# TrueTouch.net
KiCad netlist of a schematic drawn in Altium Designer
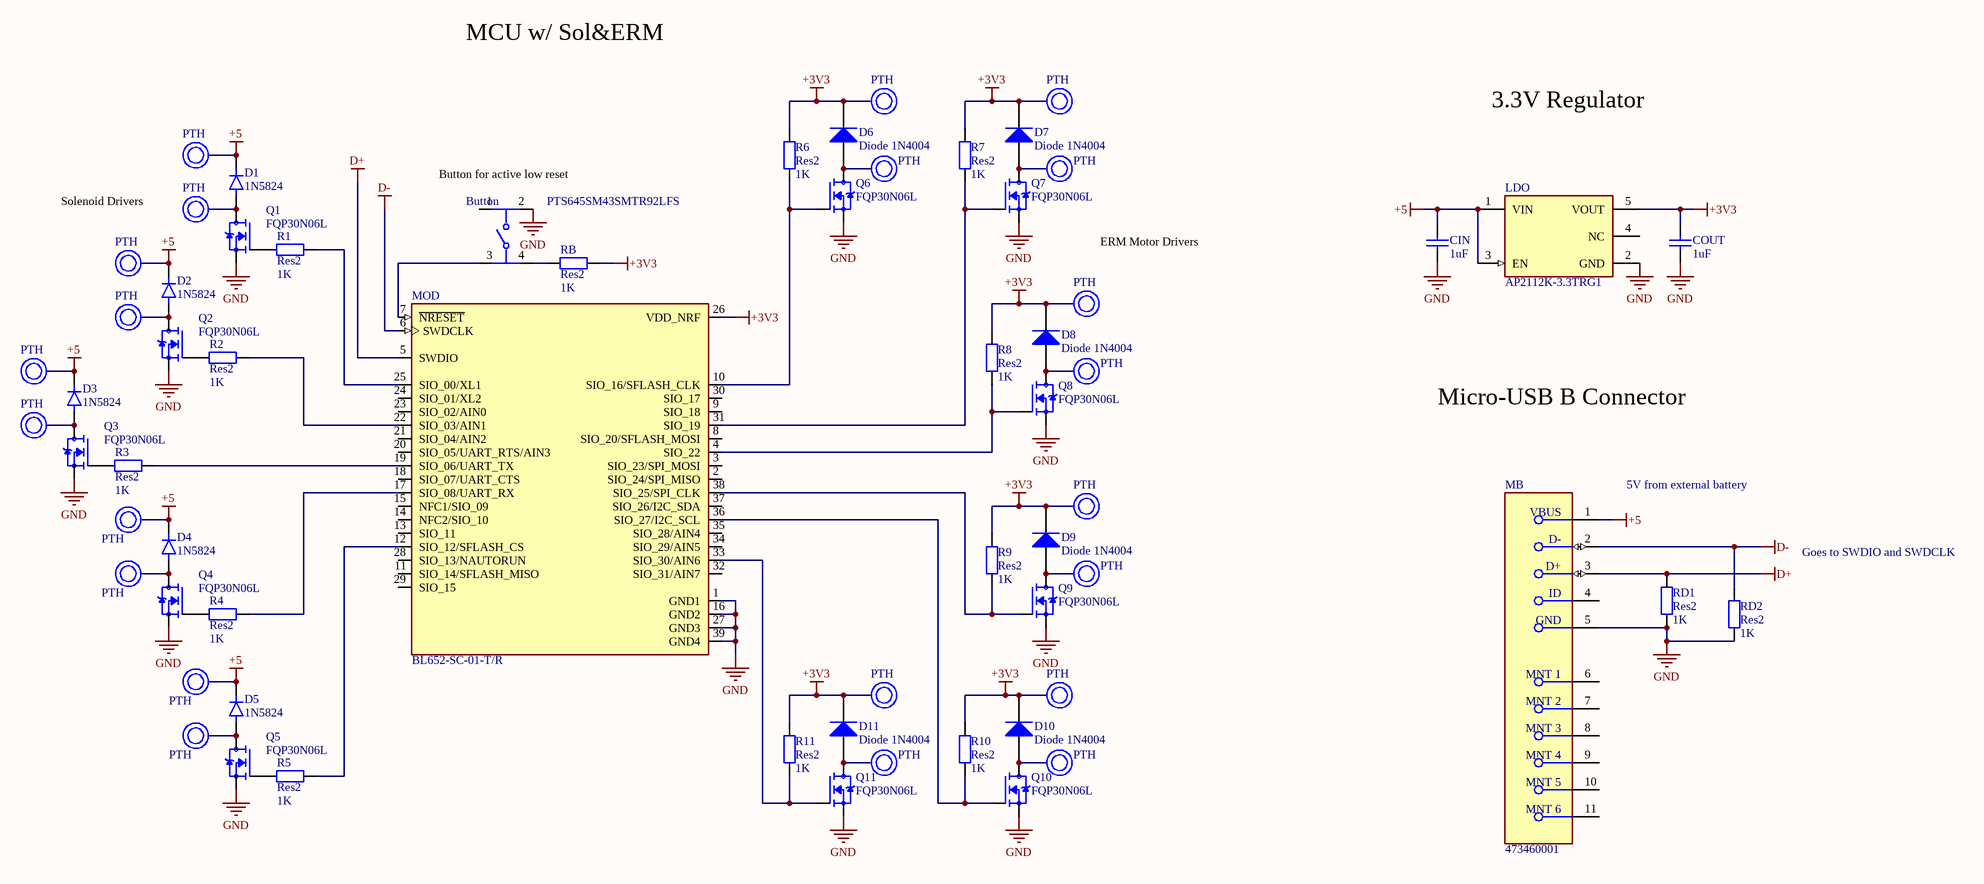
[diagram p0: TrueTouch.SchDoc]

(export (version "E")
  (design (tool "Eeschema 10.0.6"))
  (components
    (comp (ref "Button")
      (value "PTS645SM43SMTR92LFS")
      (footprint "FP-PTS645SM43SMTR92LFS-MFG")
      (description "SWITCH TACTILE SPST-NO 0.05A 12V")
      (libsource (lib "Altium Content Vault") (part "1adf0dd01260c80cf25a44bfd6b99ba"))
    )
    (comp (ref "CIN")
      (value "1uF")
      (footprint "CAPC2013X140X45NL15T25")
      (fields (field (name "PART NUMBER") "GRM21BR71E105KA99L") (field (name "MANUFACTURER") "Murata"))
      (libsource (lib "Altium Content Vault") (part "CAP"))
    )
    (comp (ref "COUT")
      (value "1uF")
      (footprint "CAPC2013X140X45NL15T25")
      (fields (field (name "PART NUMBER") "GRM21BR71E105KA99L") (field (name "MANUFACTURER") "Murata"))
      (libsource (lib "Altium Content Vault") (part "CAP"))
    )
    (comp (ref "D1")
      (value "1N5824")
      (footprint "DIOAD1898W129L762D1143")
      (description "Diode Schottky 30V 5A Through Hole Axial")
      (fields (field (name "MF") "Microsemi Corporation"))
      (libsource (lib "1N5824") (part "1N5824"))
    )
    (comp (ref "D2")
      (value "1N5824")
      (footprint "DIOAD1898W129L762D1143")
      (description "Diode Schottky 30V 5A Through Hole Axial")
      (fields (field (name "MF") "Microsemi Corporation"))
      (libsource (lib "1N5824") (part "1N5824"))
    )
    (comp (ref "D3")
      (value "1N5824")
      (footprint "DIOAD1898W129L762D1143")
      (description "Diode Schottky 30V 5A Through Hole Axial")
      (fields (field (name "MF") "Microsemi Corporation"))
      (libsource (lib "1N5824") (part "1N5824"))
    )
    (comp (ref "D4")
      (value "1N5824")
      (footprint "DIOAD1898W129L762D1143")
      (description "Diode Schottky 30V 5A Through Hole Axial")
      (fields (field (name "MF") "Microsemi Corporation"))
      (libsource (lib "1N5824") (part "1N5824"))
    )
    (comp (ref "D5")
      (value "1N5824")
      (footprint "DIOAD1898W129L762D1143")
      (description "Diode Schottky 30V 5A Through Hole Axial")
      (fields (field (name "MF") "Microsemi Corporation"))
      (libsource (lib "1N5824") (part "1N5824"))
    )
    (comp (ref "D6")
      (value "Diode 1N4004")
      (footprint "DO-41")
      (description "1 Amp General Purpose Rectifier")
      (fields (field (name "PUBLISHER") "Altium Limited"))
      (libsource (lib "Miscellaneous Devices") (part "Diode 1N4004"))
    )
    (comp (ref "D7")
      (value "Diode 1N4004")
      (footprint "DO-41")
      (description "1 Amp General Purpose Rectifier")
      (fields (field (name "PUBLISHER") "Altium Limited"))
      (libsource (lib "Miscellaneous Devices") (part "Diode 1N4004"))
    )
    (comp (ref "D8")
      (value "Diode 1N4004")
      (footprint "DO-41")
      (description "1 Amp General Purpose Rectifier")
      (fields (field (name "PUBLISHER") "Altium Limited"))
      (libsource (lib "Miscellaneous Devices") (part "Diode 1N4004"))
    )
    (comp (ref "D9")
      (value "Diode 1N4004")
      (footprint "DO-41")
      (description "1 Amp General Purpose Rectifier")
      (fields (field (name "PUBLISHER") "Altium Limited"))
      (libsource (lib "Miscellaneous Devices") (part "Diode 1N4004"))
    )
    (comp (ref "D10")
      (value "Diode 1N4004")
      (footprint "DO-41")
      (description "1 Amp General Purpose Rectifier")
      (fields (field (name "PUBLISHER") "Altium Limited"))
      (libsource (lib "Miscellaneous Devices") (part "Diode 1N4004"))
    )
    (comp (ref "D11")
      (value "Diode 1N4004")
      (footprint "DO-41")
      (description "1 Amp General Purpose Rectifier")
      (fields (field (name "PUBLISHER") "Altium Limited"))
      (libsource (lib "Miscellaneous Devices") (part "Diode 1N4004"))
    )
    (comp (ref "LDO")
      (value "AP2112K-3.3TRG1")
      (footprint "FP-SOT25-IPC_A")
      (description "IC REG LINEAR 3.3V 600MA SOT25")
      (libsource (lib "Altium Content Vault") (part "c8ab751aee5229183125ab046a11caa"))
    )
    (comp (ref "MB")
      (value "473460001")
      (footprint "FP-473460001-MFG")
      (description "CONN RCPT USB2.0 MICRO B SMD R/A")
      (fields
        (field (name "OCTOPART") "https://octopart.com/47346-0001-molex-7164928")
        (field (name "MANUFACTURER") "Molex")
      )
      (libsource (lib "Altium Content Vault") (part "53ae1f1d9b557310b43ca686e5bb76a"))
    )
    (comp (ref "MOD")
      (value "BL652-SC-01-T/R")
      (footprint "XCVR_BL652-SC-01-T/R")
      (description "Bluetooth Bluetooth v5.0 Transceiver Module 2.4GHz Antenna Not Included, I-PEX MHF4 Surface Mount")
      (fields (field (name "DIGI-KEY_PART_NUMBER") "BL652-SC-01-CT-ND") (field (name "MF") "Laird -"))
      (libsource (lib "BL652-SC-01-T_R") (part "BL652-SC-01-T/R"))
    )
    (comp (ref "Q1")
      (value "FQP30N06L")
      (footprint "TO220V")
      (description "N-Channel 60V 32A _Tc_ 79W _Tc_ Through Hole TO-220-3")
      (fields (field (name "MF") "ON Semiconductor"))
      (libsource (lib "FQP30N06L") (part "FQP30N06L"))
    )
    (comp (ref "Q2")
      (value "FQP30N06L")
      (footprint "TO220V")
      (description "N-Channel 60V 32A _Tc_ 79W _Tc_ Through Hole TO-220-3")
      (fields (field (name "MF") "ON Semiconductor"))
      (libsource (lib "FQP30N06L") (part "FQP30N06L"))
    )
    (comp (ref "Q3")
      (value "FQP30N06L")
      (footprint "TO220V")
      (description "N-Channel 60V 32A _Tc_ 79W _Tc_ Through Hole TO-220-3")
      (fields (field (name "MF") "ON Semiconductor"))
      (libsource (lib "FQP30N06L") (part "FQP30N06L"))
    )
    (comp (ref "Q4")
      (value "FQP30N06L")
      (footprint "TO220V")
      (description "N-Channel 60V 32A _Tc_ 79W _Tc_ Through Hole TO-220-3")
      (fields (field (name "MF") "ON Semiconductor"))
      (libsource (lib "FQP30N06L") (part "FQP30N06L"))
    )
    (comp (ref "Q5")
      (value "FQP30N06L")
      (footprint "TO220V")
      (description "N-Channel 60V 32A _Tc_ 79W _Tc_ Through Hole TO-220-3")
      (fields (field (name "MF") "ON Semiconductor"))
      (libsource (lib "FQP30N06L") (part "FQP30N06L"))
    )
    (comp (ref "Q6")
      (value "FQP30N06L")
      (footprint "TO220V")
      (description "N-Channel 60V 32A _Tc_ 79W _Tc_ Through Hole TO-220-3")
      (fields (field (name "MF") "ON Semiconductor"))
      (libsource (lib "FQP30N06L") (part "FQP30N06L"))
    )
    (comp (ref "Q7")
      (value "FQP30N06L")
      (footprint "TO220V")
      (description "N-Channel 60V 32A _Tc_ 79W _Tc_ Through Hole TO-220-3")
      (fields (field (name "MF") "ON Semiconductor"))
      (libsource (lib "FQP30N06L") (part "FQP30N06L"))
    )
    (comp (ref "Q8")
      (value "FQP30N06L")
      (footprint "TO220V")
      (description "N-Channel 60V 32A _Tc_ 79W _Tc_ Through Hole TO-220-3")
      (fields (field (name "MF") "ON Semiconductor"))
      (libsource (lib "FQP30N06L") (part "FQP30N06L"))
    )
    (comp (ref "Q9")
      (value "FQP30N06L")
      (footprint "TO220V")
      (description "N-Channel 60V 32A _Tc_ 79W _Tc_ Through Hole TO-220-3")
      (fields (field (name "MF") "ON Semiconductor"))
      (libsource (lib "FQP30N06L") (part "FQP30N06L"))
    )
    (comp (ref "Q10")
      (value "FQP30N06L")
      (footprint "TO220V")
      (description "N-Channel 60V 32A _Tc_ 79W _Tc_ Through Hole TO-220-3")
      (fields (field (name "MF") "ON Semiconductor"))
      (libsource (lib "FQP30N06L") (part "FQP30N06L"))
    )
    (comp (ref "Q11")
      (value "FQP30N06L")
      (footprint "TO220V")
      (description "N-Channel 60V 32A _Tc_ 79W _Tc_ Through Hole TO-220-3")
      (fields (field (name "MF") "ON Semiconductor"))
      (libsource (lib "FQP30N06L") (part "FQP30N06L"))
    )
    (comp (ref "R1")
      (value "Res2")
      (footprint "AXIAL-0.4")
      (description "Resistor")
      (fields (field (name "ALTIUM_VALUE") "1K") (field (name "PUBLISHER") "Altium Limited"))
      (libsource (lib "") (part "Res2_1"))
    )
    (comp (ref "R2")
      (value "Res2")
      (footprint "AXIAL-0.4")
      (description "Resistor")
      (fields (field (name "ALTIUM_VALUE") "1K") (field (name "PUBLISHER") "Altium Limited"))
      (libsource (lib "") (part "Res2_1"))
    )
    (comp (ref "R3")
      (value "Res2")
      (footprint "AXIAL-0.4")
      (description "Resistor")
      (fields (field (name "ALTIUM_VALUE") "1K") (field (name "PUBLISHER") "Altium Limited"))
      (libsource (lib "") (part "Res2_1"))
    )
    (comp (ref "R4")
      (value "Res2")
      (footprint "AXIAL-0.4")
      (description "Resistor")
      (fields (field (name "ALTIUM_VALUE") "1K") (field (name "PUBLISHER") "Altium Limited"))
      (libsource (lib "") (part "Res2_1"))
    )
    (comp (ref "R5")
      (value "Res2")
      (footprint "AXIAL-0.4")
      (description "Resistor")
      (fields (field (name "ALTIUM_VALUE") "1K") (field (name "PUBLISHER") "Altium Limited"))
      (libsource (lib "") (part "Res2_1"))
    )
    (comp (ref "R6")
      (value "Res2")
      (footprint "AXIAL-0.4")
      (description "Resistor")
      (fields (field (name "ALTIUM_VALUE") "1K") (field (name "PUBLISHER") "Altium Limited"))
      (libsource (lib "Miscellaneous Devices") (part "Res2"))
    )
    (comp (ref "R7")
      (value "Res2")
      (footprint "AXIAL-0.4")
      (description "Resistor")
      (fields (field (name "ALTIUM_VALUE") "1K") (field (name "PUBLISHER") "Altium Limited"))
      (libsource (lib "Miscellaneous Devices") (part "Res2"))
    )
    (comp (ref "R8")
      (value "Res2")
      (footprint "AXIAL-0.4")
      (description "Resistor")
      (fields (field (name "ALTIUM_VALUE") "1K") (field (name "PUBLISHER") "Altium Limited"))
      (libsource (lib "Miscellaneous Devices") (part "Res2"))
    )
    (comp (ref "R9")
      (value "Res2")
      (footprint "AXIAL-0.4")
      (description "Resistor")
      (fields (field (name "ALTIUM_VALUE") "1K") (field (name "PUBLISHER") "Altium Limited"))
      (libsource (lib "Miscellaneous Devices") (part "Res2"))
    )
    (comp (ref "R10")
      (value "Res2")
      (footprint "AXIAL-0.4")
      (description "Resistor")
      (fields (field (name "ALTIUM_VALUE") "1K") (field (name "PUBLISHER") "Altium Limited"))
      (libsource (lib "Miscellaneous Devices") (part "Res2"))
    )
    (comp (ref "R11")
      (value "Res2")
      (footprint "AXIAL-0.4")
      (description "Resistor")
      (fields (field (name "ALTIUM_VALUE") "1K") (field (name "PUBLISHER") "Altium Limited"))
      (libsource (lib "Miscellaneous Devices") (part "Res2"))
    )
    (comp (ref "RB")
      (value "Res2")
      (footprint "AXIAL-0.4")
      (description "Resistor")
      (fields (field (name "ALTIUM_VALUE") "1K") (field (name "PUBLISHER") "Altium Limited"))
      (libsource (lib "") (part "Res2_1"))
    )
    (comp (ref "RD1")
      (value "Res2")
      (footprint "AXIAL-0.4")
      (description "Resistor")
      (fields (field (name "ALTIUM_VALUE") "1K") (field (name "PUBLISHER") "Altium Limited"))
      (libsource (lib "Miscellaneous Devices") (part "Res2"))
    )
    (comp (ref "RD2")
      (value "Res2")
      (footprint "AXIAL-0.4")
      (description "Resistor")
      (fields (field (name "ALTIUM_VALUE") "1K") (field (name "PUBLISHER") "Altium Limited"))
      (libsource (lib "Miscellaneous Devices") (part "Res2"))
    )
  )
  (nets
    (net (code "1") (name "+3V3") (class "Default")
      (node (ref "COUT") (pin "2") (pinfunction "2_2") (pintype "passive"))
      (node (ref "D10") (pin "2") (pinfunction "K_2") (pintype "passive"))
      (node (ref "D11") (pin "2") (pinfunction "K_2") (pintype "passive"))
      (node (ref "D6") (pin "2") (pinfunction "K_2") (pintype "passive"))
      (node (ref "D7") (pin "2") (pinfunction "K_2") (pintype "passive"))
      (node (ref "D8") (pin "2") (pinfunction "K_2") (pintype "passive"))
      (node (ref "D9") (pin "2") (pinfunction "K_2") (pintype "passive"))
      (node (ref "LDO") (pin "5") (pinfunction "VOUT_5") (pintype "power_in"))
      (node (ref "MOD") (pin "26") (pinfunction "VDD_NRF_26") (pintype "power_in"))
      (node (ref "R10") (pin "1") (pinfunction "1_1") (pintype "passive"))
      (node (ref "R11") (pin "1") (pinfunction "1_1") (pintype "passive"))
      (node (ref "R6") (pin "1") (pinfunction "1_1") (pintype "passive"))
      (node (ref "R7") (pin "1") (pinfunction "1_1") (pintype "passive"))
      (node (ref "R8") (pin "1") (pinfunction "1_1") (pintype "passive"))
      (node (ref "R9") (pin "1") (pinfunction "1_1") (pintype "passive"))
      (node (ref "RB") (pin "2") (pinfunction "2_2") (pintype "passive"))
    )
    (net (code "2") (name "+5") (class "Default")
      (node (ref "CIN") (pin "2") (pinfunction "2_2") (pintype "passive"))
      (node (ref "D1") (pin "C") (pinfunction "K_C") (pintype "passive"))
      (node (ref "D2") (pin "C") (pinfunction "K_C") (pintype "passive"))
      (node (ref "D3") (pin "C") (pinfunction "K_C") (pintype "passive"))
      (node (ref "D4") (pin "C") (pinfunction "K_C") (pintype "passive"))
      (node (ref "D5") (pin "C") (pinfunction "K_C") (pintype "passive"))
      (node (ref "LDO") (pin "1") (pinfunction "VIN_1") (pintype "power_in"))
      (node (ref "LDO") (pin "3") (pinfunction "EN_3") (pintype "input"))
      (node (ref "MB") (pin "1") (pinfunction "VBUS_1") (pintype "power_in"))
    )
    (net (code "3") (name "D+") (class "Default")
      (node (ref "MB") (pin "3") (pinfunction "D+_3") (pintype "bidirectional"))
      (node (ref "MOD") (pin "5") (pinfunction "SWDIO_5") (pintype "bidirectional"))
      (node (ref "RD1") (pin "1") (pinfunction "1_1") (pintype "passive"))
    )
    (net (code "4") (name "D-") (class "Default")
      (node (ref "MB") (pin "2") (pinfunction "D-_2") (pintype "bidirectional"))
      (node (ref "MOD") (pin "6") (pinfunction "SWDCLK_6") (pintype "input"))
      (node (ref "RD2") (pin "1") (pinfunction "1_1") (pintype "passive"))
    )
    (net (code "5") (name "GND") (class "Default")
      (node (ref "Button") (pin "2") (pinfunction "2_2") (pintype "passive"))
      (node (ref "CIN") (pin "1") (pinfunction "1_1") (pintype "passive"))
      (node (ref "COUT") (pin "1") (pinfunction "1_1") (pintype "passive"))
      (node (ref "LDO") (pin "2") (pinfunction "GND_2") (pintype "power_in"))
      (node (ref "MB") (pin "5") (pinfunction "GND_5") (pintype "power_in"))
      (node (ref "MOD") (pin "1") (pinfunction "GND1_1") (pintype "power_in"))
      (node (ref "MOD") (pin "16") (pinfunction "GND2_16") (pintype "power_in"))
      (node (ref "MOD") (pin "27") (pinfunction "GND3_27") (pintype "power_in"))
      (node (ref "MOD") (pin "39") (pinfunction "GND4_39") (pintype "power_in"))
      (node (ref "Q1") (pin "3") (pinfunction "S_3") (pintype "passive"))
      (node (ref "Q10") (pin "3") (pinfunction "S_3") (pintype "passive"))
      (node (ref "Q11") (pin "3") (pinfunction "S_3") (pintype "passive"))
      (node (ref "Q2") (pin "3") (pinfunction "S_3") (pintype "passive"))
      (node (ref "Q3") (pin "3") (pinfunction "S_3") (pintype "passive"))
      (node (ref "Q4") (pin "3") (pinfunction "S_3") (pintype "passive"))
      (node (ref "Q5") (pin "3") (pinfunction "S_3") (pintype "passive"))
      (node (ref "Q6") (pin "3") (pinfunction "S_3") (pintype "passive"))
      (node (ref "Q7") (pin "3") (pinfunction "S_3") (pintype "passive"))
      (node (ref "Q8") (pin "3") (pinfunction "S_3") (pintype "passive"))
      (node (ref "Q9") (pin "3") (pinfunction "S_3") (pintype "passive"))
      (node (ref "RD1") (pin "2") (pinfunction "2_2") (pintype "passive"))
      (node (ref "RD2") (pin "2") (pinfunction "2_2") (pintype "passive"))
    )
    (net (code "6") (name "Net-(Button-Pad4)") (class "Default")
      (node (ref "Button") (pin "4") (pinfunction "4_4") (pintype "passive"))
      (node (ref "RB") (pin "1") (pinfunction "1_1") (pintype "passive"))
    )
    (net (code "7") (name "Net-(D6-A)") (class "Default")
      (node (ref "D6") (pin "1") (pinfunction "A_1") (pintype "passive"))
      (node (ref "Q6") (pin "2") (pinfunction "D_2") (pintype "passive"))
    )
    (net (code "8") (name "Net-(D7-A)") (class "Default")
      (node (ref "D7") (pin "1") (pinfunction "A_1") (pintype "passive"))
      (node (ref "Q7") (pin "2") (pinfunction "D_2") (pintype "passive"))
    )
    (net (code "9") (name "Net-(D8-A)") (class "Default")
      (node (ref "D8") (pin "1") (pinfunction "A_1") (pintype "passive"))
      (node (ref "Q8") (pin "2") (pinfunction "D_2") (pintype "passive"))
    )
    (net (code "10") (name "Net-(D9-A)") (class "Default")
      (node (ref "D9") (pin "1") (pinfunction "A_1") (pintype "passive"))
      (node (ref "Q9") (pin "2") (pinfunction "D_2") (pintype "passive"))
    )
    (net (code "11") (name "Net-(D10-A)") (class "Default")
      (node (ref "D10") (pin "1") (pinfunction "A_1") (pintype "passive"))
      (node (ref "Q10") (pin "2") (pinfunction "D_2") (pintype "passive"))
    )
    (net (code "12") (name "Net-(D11-A)") (class "Default")
      (node (ref "D11") (pin "1") (pinfunction "A_1") (pintype "passive"))
      (node (ref "Q11") (pin "2") (pinfunction "D_2") (pintype "passive"))
    )
    (net (code "13") (name "Net-(MOD-SIO_00{slash}XL1)") (class "Default")
      (node (ref "MOD") (pin "25") (pinfunction "SIO_00/XL1_25") (pintype "bidirectional"))
      (node (ref "R1") (pin "2") (pinfunction "2_2") (pintype "passive"))
    )
    (net (code "14") (name "Net-(MOD-SIO_03{slash}AIN1)") (class "Default")
      (node (ref "MOD") (pin "22") (pinfunction "SIO_03/AIN1_22") (pintype "bidirectional"))
      (node (ref "R2") (pin "2") (pinfunction "2_2") (pintype "passive"))
    )
    (net (code "15") (name "Net-(MOD-SIO_06{slash}UART_TX)") (class "Default")
      (node (ref "MOD") (pin "19") (pinfunction "SIO_06/UART_TX_19") (pintype "bidirectional"))
      (node (ref "R3") (pin "2") (pinfunction "2_2") (pintype "passive"))
    )
    (net (code "16") (name "Net-(MOD-SIO_08{slash}UART_RX)") (class "Default")
      (node (ref "MOD") (pin "17") (pinfunction "SIO_08/UART_RX_17") (pintype "bidirectional"))
      (node (ref "R4") (pin "2") (pinfunction "2_2") (pintype "passive"))
    )
    (net (code "17") (name "Net-(MOD-SIO_12{slash}SFLASH_CS)") (class "Default")
      (node (ref "MOD") (pin "12") (pinfunction "SIO_12/SFLASH_CS_12") (pintype "bidirectional"))
      (node (ref "R5") (pin "2") (pinfunction "2_2") (pintype "passive"))
    )
    (net (code "18") (name "Net-(MOD-SIO_16{slash}SFLASH_CLK)") (class "Default")
      (node (ref "MOD") (pin "10") (pinfunction "SIO_16/SFLASH_CLK_10") (pintype "bidirectional"))
      (node (ref "Q6") (pin "1") (pinfunction "G_1") (pintype "passive"))
      (node (ref "R6") (pin "2") (pinfunction "2_2") (pintype "passive"))
    )
    (net (code "19") (name "Net-(MOD-SIO_19)") (class "Default")
      (node (ref "MOD") (pin "31") (pinfunction "SIO_19_31") (pintype "bidirectional"))
      (node (ref "Q7") (pin "1") (pinfunction "G_1") (pintype "passive"))
      (node (ref "R7") (pin "2") (pinfunction "2_2") (pintype "passive"))
    )
    (net (code "20") (name "Net-(MOD-SIO_22)") (class "Default")
      (node (ref "MOD") (pin "4") (pinfunction "SIO_22_4") (pintype "bidirectional"))
      (node (ref "Q8") (pin "1") (pinfunction "G_1") (pintype "passive"))
      (node (ref "R8") (pin "2") (pinfunction "2_2") (pintype "passive"))
    )
    (net (code "21") (name "Net-(MOD-SIO_25{slash}SPI_CLK)") (class "Default")
      (node (ref "MOD") (pin "38") (pinfunction "SIO_25/SPI_CLK_38") (pintype "bidirectional"))
      (node (ref "Q9") (pin "1") (pinfunction "G_1") (pintype "passive"))
      (node (ref "R9") (pin "2") (pinfunction "2_2") (pintype "passive"))
    )
    (net (code "22") (name "Net-(MOD-SIO_27{slash}I2C_SCL)") (class "Default")
      (node (ref "MOD") (pin "36") (pinfunction "SIO_27/I2C_SCL_36") (pintype "bidirectional"))
      (node (ref "Q10") (pin "1") (pinfunction "G_1") (pintype "passive"))
      (node (ref "R10") (pin "2") (pinfunction "2_2") (pintype "passive"))
    )
    (net (code "23") (name "Net-(MOD-SIO_30{slash}AIN6)") (class "Default")
      (node (ref "MOD") (pin "33") (pinfunction "SIO_30/AIN6_33") (pintype "bidirectional"))
      (node (ref "Q11") (pin "1") (pinfunction "G_1") (pintype "passive"))
      (node (ref "R11") (pin "2") (pinfunction "2_2") (pintype "passive"))
    )
    (net (code "24") (name "Net-(MOD-~{NRESET})") (class "Default")
      (node (ref "Button") (pin "3") (pinfunction "3_3") (pintype "passive"))
      (node (ref "MOD") (pin "7") (pinfunction "~{NRESET}_7") (pintype "input"))
    )
    (net (code "25") (name "Net-(Q1-D)") (class "Default")
      (node (ref "D1") (pin "A") (pinfunction "A_A") (pintype "passive"))
      (node (ref "Q1") (pin "2") (pinfunction "D_2") (pintype "passive"))
    )
    (net (code "26") (name "Net-(Q1-G)") (class "Default")
      (node (ref "Q1") (pin "1") (pinfunction "G_1") (pintype "passive"))
      (node (ref "R1") (pin "1") (pinfunction "1_1") (pintype "passive"))
    )
    (net (code "27") (name "Net-(Q2-D)") (class "Default")
      (node (ref "D2") (pin "A") (pinfunction "A_A") (pintype "passive"))
      (node (ref "Q2") (pin "2") (pinfunction "D_2") (pintype "passive"))
    )
    (net (code "28") (name "Net-(Q2-G)") (class "Default")
      (node (ref "Q2") (pin "1") (pinfunction "G_1") (pintype "passive"))
      (node (ref "R2") (pin "1") (pinfunction "1_1") (pintype "passive"))
    )
    (net (code "29") (name "Net-(Q3-D)") (class "Default")
      (node (ref "D3") (pin "A") (pinfunction "A_A") (pintype "passive"))
      (node (ref "Q3") (pin "2") (pinfunction "D_2") (pintype "passive"))
    )
    (net (code "30") (name "Net-(Q3-G)") (class "Default")
      (node (ref "Q3") (pin "1") (pinfunction "G_1") (pintype "passive"))
      (node (ref "R3") (pin "1") (pinfunction "1_1") (pintype "passive"))
    )
    (net (code "31") (name "Net-(Q4-D)") (class "Default")
      (node (ref "D4") (pin "A") (pinfunction "A_A") (pintype "passive"))
      (node (ref "Q4") (pin "2") (pinfunction "D_2") (pintype "passive"))
    )
    (net (code "32") (name "Net-(Q4-G)") (class "Default")
      (node (ref "Q4") (pin "1") (pinfunction "G_1") (pintype "passive"))
      (node (ref "R4") (pin "1") (pinfunction "1_1") (pintype "passive"))
    )
    (net (code "33") (name "Net-(Q5-D)") (class "Default")
      (node (ref "D5") (pin "A") (pinfunction "A_A") (pintype "passive"))
      (node (ref "Q5") (pin "2") (pinfunction "D_2") (pintype "passive"))
    )
    (net (code "34") (name "Net-(Q5-G)") (class "Default")
      (node (ref "Q5") (pin "1") (pinfunction "G_1") (pintype "passive"))
      (node (ref "R5") (pin "1") (pinfunction "1_1") (pintype "passive"))
    )
    (net (code "35") (name "unconnected-(Button-Pad1)") (class "Default")
      (node (ref "Button") (pin "1") (pinfunction "1_1") (pintype "passive"))
    )
    (net (code "36") (name "unconnected-(LDO-NC-Pad4)") (class "Default")
      (node (ref "LDO") (pin "4") (pinfunction "NC_4") (pintype "passive"))
    )
    (net (code "37") (name "unconnected-(MB-ID-Pad4)") (class "Default")
      (node (ref "MB") (pin "4") (pinfunction "ID_4") (pintype "passive"))
    )
    (net (code "38") (name "unconnected-(MB-MNT_1-Pad6)") (class "Default")
      (node (ref "MB") (pin "6") (pinfunction "MNT_1_6") (pintype "passive"))
    )
    (net (code "39") (name "unconnected-(MB-MNT_2-Pad7)") (class "Default")
      (node (ref "MB") (pin "7") (pinfunction "MNT_2_7") (pintype "passive"))
    )
    (net (code "40") (name "unconnected-(MB-MNT_3-Pad8)") (class "Default")
      (node (ref "MB") (pin "8") (pinfunction "MNT_3_8") (pintype "passive"))
    )
    (net (code "41") (name "unconnected-(MB-MNT_4-Pad9)") (class "Default")
      (node (ref "MB") (pin "9") (pinfunction "MNT_4_9") (pintype "passive"))
    )
    (net (code "42") (name "unconnected-(MB-MNT_5-Pad10)") (class "Default")
      (node (ref "MB") (pin "10") (pinfunction "MNT_5_10") (pintype "passive"))
    )
    (net (code "43") (name "unconnected-(MB-MNT_6-Pad11)") (class "Default")
      (node (ref "MB") (pin "11") (pinfunction "MNT_6_11") (pintype "passive"))
    )
    (net (code "44") (name "unconnected-(MOD-NFC1{slash}SIO_09-Pad15)") (class "Default")
      (node (ref "MOD") (pin "15") (pinfunction "NFC1/SIO_09_15") (pintype "bidirectional"))
    )
    (net (code "45") (name "unconnected-(MOD-NFC2{slash}SIO_10-Pad14)") (class "Default")
      (node (ref "MOD") (pin "14") (pinfunction "NFC2/SIO_10_14") (pintype "bidirectional"))
    )
    (net (code "46") (name "unconnected-(MOD-SIO_01{slash}XL2-Pad24)") (class "Default")
      (node (ref "MOD") (pin "24") (pinfunction "SIO_01/XL2_24") (pintype "bidirectional"))
    )
    (net (code "47") (name "unconnected-(MOD-SIO_02{slash}AIN0-Pad23)") (class "Default")
      (node (ref "MOD") (pin "23") (pinfunction "SIO_02/AIN0_23") (pintype "bidirectional"))
    )
    (net (code "48") (name "unconnected-(MOD-SIO_04{slash}AIN2-Pad21)") (class "Default")
      (node (ref "MOD") (pin "21") (pinfunction "SIO_04/AIN2_21") (pintype "bidirectional"))
    )
    (net (code "49") (name "unconnected-(MOD-SIO_05{slash}UART_RTS{slash}AIN3-Pad20)") (class "Default")
      (node (ref "MOD") (pin "20") (pinfunction "SIO_05/UART_RTS/AIN3_20") (pintype "bidirectional"))
    )
    (net (code "50") (name "unconnected-(MOD-SIO_07{slash}UART_CTS-Pad18)") (class "Default")
      (node (ref "MOD") (pin "18") (pinfunction "SIO_07/UART_CTS_18") (pintype "bidirectional"))
    )
    (net (code "51") (name "unconnected-(MOD-SIO_11-Pad13)") (class "Default")
      (node (ref "MOD") (pin "13") (pinfunction "SIO_11_13") (pintype "bidirectional"))
    )
    (net (code "52") (name "unconnected-(MOD-SIO_13{slash}NAUTORUN-Pad28)") (class "Default")
      (node (ref "MOD") (pin "28") (pinfunction "SIO_13/NAUTORUN_28") (pintype "bidirectional"))
    )
    (net (code "53") (name "unconnected-(MOD-SIO_14{slash}SFLASH_MISO-Pad11)") (class "Default")
      (node (ref "MOD") (pin "11") (pinfunction "SIO_14/SFLASH_MISO_11") (pintype "bidirectional"))
    )
    (net (code "54") (name "unconnected-(MOD-SIO_15-Pad29)") (class "Default")
      (node (ref "MOD") (pin "29") (pinfunction "SIO_15_29") (pintype "bidirectional"))
    )
    (net (code "55") (name "unconnected-(MOD-SIO_17-Pad30)") (class "Default")
      (node (ref "MOD") (pin "30") (pinfunction "SIO_17_30") (pintype "bidirectional"))
    )
    (net (code "56") (name "unconnected-(MOD-SIO_18-Pad9)") (class "Default")
      (node (ref "MOD") (pin "9") (pinfunction "SIO_18_9") (pintype "bidirectional"))
    )
    (net (code "57") (name "unconnected-(MOD-SIO_20{slash}SFLASH_MOSI-Pad8)") (class "Default")
      (node (ref "MOD") (pin "8") (pinfunction "SIO_20/SFLASH_MOSI_8") (pintype "bidirectional"))
    )
    (net (code "58") (name "unconnected-(MOD-SIO_23{slash}SPI_MOSI-Pad3)") (class "Default")
      (node (ref "MOD") (pin "3") (pinfunction "SIO_23/SPI_MOSI_3") (pintype "bidirectional"))
    )
    (net (code "59") (name "unconnected-(MOD-SIO_24{slash}SPI_MISO-Pad2)") (class "Default")
      (node (ref "MOD") (pin "2") (pinfunction "SIO_24/SPI_MISO_2") (pintype "bidirectional"))
    )
    (net (code "60") (name "unconnected-(MOD-SIO_26{slash}I2C_SDA-Pad37)") (class "Default")
      (node (ref "MOD") (pin "37") (pinfunction "SIO_26/I2C_SDA_37") (pintype "bidirectional"))
    )
    (net (code "61") (name "unconnected-(MOD-SIO_28{slash}AIN4-Pad35)") (class "Default")
      (node (ref "MOD") (pin "35") (pinfunction "SIO_28/AIN4_35") (pintype "bidirectional"))
    )
    (net (code "62") (name "unconnected-(MOD-SIO_29{slash}AIN5-Pad34)") (class "Default")
      (node (ref "MOD") (pin "34") (pinfunction "SIO_29/AIN5_34") (pintype "bidirectional"))
    )
    (net (code "63") (name "unconnected-(MOD-SIO_31{slash}AIN7-Pad32)") (class "Default")
      (node (ref "MOD") (pin "32") (pinfunction "SIO_31/AIN7_32") (pintype "bidirectional"))
    )
  )
)
